# 03_USB.net
KiCad netlist of a schematic drawn in Altium Designer
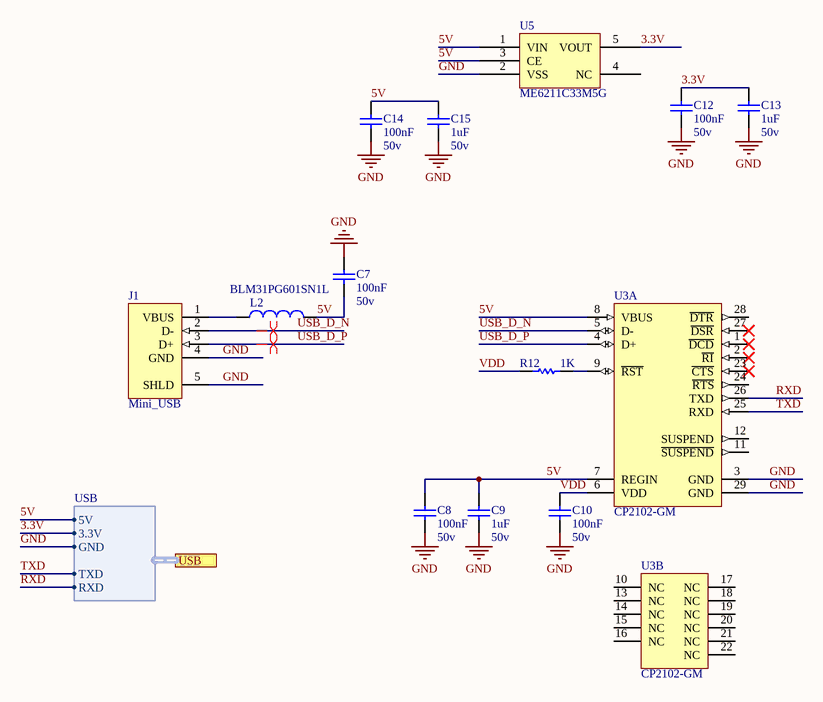
[diagram p0: [03] USB.SchDoc]

(export (version "E")
  (design (tool "Eeschema 10.0.6"))
  (components
    (comp (ref "C7")
      (value "100nF")
      (footprint "MY_0603")
      (description "None polar capacitor")
      (fields (field (name "ASID PART NUMBER") "C-AS") (field (name "VOLTE") "50v"))
      (libsource (lib "Mylib Rev 4") (part "Cap ceramic"))
    )
    (comp (ref "C8")
      (value "100nF")
      (footprint "MY_0603")
      (description "None polar capacitor")
      (fields (field (name "ASID PART NUMBER") "C-AS") (field (name "VOLTE") "50v"))
      (libsource (lib "Mylib Rev 4") (part "Cap ceramic"))
    )
    (comp (ref "C9")
      (value "1uF")
      (footprint "MY_0603")
      (description "None polar capacitor")
      (fields (field (name "ASID PART NUMBER") "C-AS") (field (name "VOLTE") "50v"))
      (libsource (lib "Mylib Rev 4") (part "Cap ceramic"))
    )
    (comp (ref "C10")
      (value "100nF")
      (footprint "MY_0603")
      (description "None polar capacitor")
      (fields (field (name "ASID PART NUMBER") "C-AS") (field (name "VOLTE") "50v"))
      (libsource (lib "Mylib Rev 4") (part "Cap ceramic"))
    )
    (comp (ref "C12")
      (value "100nF")
      (footprint "MY_0603")
      (description "None polar capacitor")
      (fields (field (name "ASID PART NUMBER") "C-AS") (field (name "VOLTE") "50v"))
      (libsource (lib "Mylib Rev 4") (part "Cap ceramic"))
    )
    (comp (ref "C13")
      (value "1uF")
      (footprint "MY_0603")
      (description "None polar capacitor")
      (fields (field (name "ASID PART NUMBER") "C-AS") (field (name "VOLTE") "50v"))
      (libsource (lib "Mylib Rev 4") (part "Cap ceramic"))
    )
    (comp (ref "C14")
      (value "100nF")
      (footprint "MY_0603")
      (description "None polar capacitor")
      (fields (field (name "ASID PART NUMBER") "C-AS") (field (name "VOLTE") "50v"))
      (libsource (lib "Mylib Rev 4") (part "Cap ceramic"))
    )
    (comp (ref "C15")
      (value "1uF")
      (footprint "MY_0603")
      (description "None polar capacitor")
      (fields (field (name "ASID PART NUMBER") "C-AS") (field (name "VOLTE") "50v"))
      (libsource (lib "Mylib Rev 4") (part "Cap ceramic"))
    )
    (comp (ref "J1")
      (value "Mini_USB")
      (footprint "MY_Micro_USB_B")
      (description "USB 2.0, Right Angle, SMT, B Type, Receptacle, 5 Position, Black")
      (fields (field (name "ASID PART NUMBER") "Mini_USB-AS"))
      (libsource (lib "Mylib Rev 4") (part "Mini_USB"))
    )
    (comp (ref "L2")
      (value "BLM31PG601SN1L")
      (footprint "MY_1206")
      (description "Inductor")
      (fields (field (name "ASID PART NUMBER") "Inductor-AS"))
      (libsource (lib "Mylib Rev 4") (part "Inductor"))
    )
    (comp (ref "R12")
      (value "1K")
      (footprint "MY_0603")
      (description "Standard resistor")
      (fields (field (name "ASID PART NUMBER") "Res-AS"))
      (libsource (lib "Mylib Rev 4") (part "Res"))
    )
    (comp (ref "U3")
      (value "CP2102-GM")
      (footprint "SLAB-QFN-28-3125x3125TP_N")
      (description "Single-Chip USB to UART Bridge, 1024 Bytes EEPROM, -40 to 85 degC, 28-pin QFN, Tube")
      (fields (field (name "MANUFACTURER") "Silicon Labs"))
      (libsource (lib "Altium Content Vault") (part "SLAB-CP210X-QFN-28-29"))
    )
    (comp (ref "U5")
      (value "ME6211C33M5G")
      (footprint "MY_SOT23-5")
      (description "High Speed LDO Regulators, High PSRR, Low noise")
      (libsource (lib "Mylib Rev 4") (part "ME6211C33M5G"))
    )
  )
  (nets
    (net (code "2") (name "/3.3V") (class "Default")
      (node (ref "C12") (pin "1") (pinfunction "1_1") (pintype "passive"))
      (node (ref "C13") (pin "1") (pinfunction "1_1") (pintype "passive"))
      (node (ref "U5") (pin "5") (pinfunction "VOUT_5") (pintype "power_in"))
    )
    (net (code "3") (name "/5V") (class "Default")
      (node (ref "C14") (pin "1") (pinfunction "1_1") (pintype "passive"))
      (node (ref "C15") (pin "2") (pinfunction "2_2") (pintype "passive"))
      (node (ref "C7") (pin "2") (pinfunction "2_2") (pintype "passive"))
      (node (ref "C8") (pin "2") (pinfunction "2_2") (pintype "passive"))
      (node (ref "C9") (pin "2") (pinfunction "2_2") (pintype "passive"))
      (node (ref "L2") (pin "2") (pinfunction "2_2") (pintype "passive"))
      (node (ref "U3") (pin "7") (pinfunction "REGIN_7") (pintype "power_in"))
      (node (ref "U3") (pin "8") (pinfunction "VBUS_8") (pintype "input"))
      (node (ref "U5") (pin "1") (pinfunction "VIN_1") (pintype "power_in"))
      (node (ref "U5") (pin "3") (pinfunction "CE_3") (pintype "passive"))
    )
    (net (code "4") (name "/RXD") (class "Default")
      (node (ref "U3") (pin "26") (pinfunction "TXD_26") (pintype "output"))
    )
    (net (code "5") (name "/TXD") (class "Default")
      (node (ref "U3") (pin "25") (pinfunction "RXD_25") (pintype "input"))
    )
    (net (code "6") (name "/USB_D_N") (class "Default")
      (node (ref "J1") (pin "2") (pinfunction "D-_2") (pintype "input"))
      (node (ref "U3") (pin "5") (pinfunction "D-_5") (pintype "bidirectional"))
    )
    (net (code "7") (name "/USB_D_P") (class "Default")
      (node (ref "J1") (pin "3") (pinfunction "D+_3") (pintype "input"))
      (node (ref "U3") (pin "4") (pinfunction "D+_4") (pintype "bidirectional"))
    )
    (net (code "8") (name "/VDD") (class "Default")
      (node (ref "C10") (pin "2") (pinfunction "2_2") (pintype "passive"))
      (node (ref "R12") (pin "1") (pinfunction "1_1") (pintype "passive"))
      (node (ref "U3") (pin "6") (pinfunction "VDD_6") (pintype "power_in"))
    )
    (net (code "10") (name "GND") (class "Default")
      (node (ref "C10") (pin "1") (pinfunction "1_1") (pintype "passive"))
      (node (ref "C12") (pin "2") (pinfunction "2_2") (pintype "passive"))
      (node (ref "C13") (pin "2") (pinfunction "2_2") (pintype "passive"))
      (node (ref "C14") (pin "2") (pinfunction "2_2") (pintype "passive"))
      (node (ref "C15") (pin "1") (pinfunction "1_1") (pintype "passive"))
      (node (ref "C7") (pin "1") (pinfunction "1_1") (pintype "passive"))
      (node (ref "C8") (pin "1") (pinfunction "1_1") (pintype "passive"))
      (node (ref "C9") (pin "1") (pinfunction "1_1") (pintype "passive"))
      (node (ref "J1") (pin "4") (pinfunction "GND_4") (pintype "power_in"))
      (node (ref "J1") (pin "5") (pinfunction "SHLD_5") (pintype "passive"))
      (node (ref "U3") (pin "29") (pinfunction "GND_29") (pintype "power_in"))
      (node (ref "U3") (pin "3") (pinfunction "GND_3") (pintype "power_in"))
      (node (ref "U5") (pin "2") (pinfunction "VSS_2") (pintype "power_in"))
    )
    (net (code "11") (name "Net-(J1-VBUS)") (class "Default")
      (node (ref "J1") (pin "1") (pinfunction "VBUS_1") (pintype "power_in"))
      (node (ref "L2") (pin "1") (pinfunction "1_1") (pintype "passive"))
    )
    (net (code "12") (name "Net-(U3A-~{RST})") (class "Default")
      (node (ref "R12") (pin "2") (pinfunction "2_2") (pintype "passive"))
      (node (ref "U3") (pin "9") (pinfunction "~{RST}_9") (pintype "bidirectional"))
    )
    (net (code "13") (name "unconnected-(U3A-SUSPEND-Pad12)") (class "Default")
      (node (ref "U3") (pin "12") (pinfunction "SUSPEND_12") (pintype "output"))
    )
    (net (code "14") (name "unconnected-(U3A-~{CTS}-Pad23)") (class "Default")
      (node (ref "U3") (pin "23") (pinfunction "~{CTS}_23") (pintype "input+no_connect"))
    )
    (net (code "15") (name "unconnected-(U3A-~{DCD}-Pad1)") (class "Default")
      (node (ref "U3") (pin "1") (pinfunction "~{DCD}_1") (pintype "input+no_connect"))
    )
    (net (code "16") (name "unconnected-(U3A-~{DSR}-Pad27)") (class "Default")
      (node (ref "U3") (pin "27") (pinfunction "~{DSR}_27") (pintype "input+no_connect"))
    )
    (net (code "17") (name "unconnected-(U3A-~{DTR}-Pad28)") (class "Default")
      (node (ref "U3") (pin "28") (pinfunction "~{DTR}_28") (pintype "output"))
    )
    (net (code "18") (name "unconnected-(U3A-~{RI}-Pad2)") (class "Default")
      (node (ref "U3") (pin "2") (pinfunction "~{RI}_2") (pintype "input+no_connect"))
    )
    (net (code "19") (name "unconnected-(U3A-~{RTS}-Pad24)") (class "Default")
      (node (ref "U3") (pin "24") (pinfunction "~{RTS}_24") (pintype "output"))
    )
    (net (code "20") (name "unconnected-(U3A-~{SUSPEND}-Pad11)") (class "Default")
      (node (ref "U3") (pin "11") (pinfunction "~{SUSPEND}_11") (pintype "output"))
    )
    (net (code "21") (name "unconnected-(U3B-NC-Pad10)") (class "Default")
      (node (ref "U3") (pin "10") (pinfunction "NC_10") (pintype "passive"))
    )
    (net (code "22") (name "unconnected-(U3B-NC-Pad13)") (class "Default")
      (node (ref "U3") (pin "13") (pinfunction "NC_13") (pintype "passive"))
    )
    (net (code "23") (name "unconnected-(U3B-NC-Pad14)") (class "Default")
      (node (ref "U3") (pin "14") (pinfunction "NC_14") (pintype "passive"))
    )
    (net (code "24") (name "unconnected-(U3B-NC-Pad15)") (class "Default")
      (node (ref "U3") (pin "15") (pinfunction "NC_15") (pintype "passive"))
    )
    (net (code "25") (name "unconnected-(U3B-NC-Pad16)") (class "Default")
      (node (ref "U3") (pin "16") (pinfunction "NC_16") (pintype "passive"))
    )
    (net (code "26") (name "unconnected-(U3B-NC-Pad17)") (class "Default")
      (node (ref "U3") (pin "17") (pinfunction "NC_17") (pintype "passive"))
    )
    (net (code "27") (name "unconnected-(U3B-NC-Pad18)") (class "Default")
      (node (ref "U3") (pin "18") (pinfunction "NC_18") (pintype "passive"))
    )
    (net (code "28") (name "unconnected-(U3B-NC-Pad19)") (class "Default")
      (node (ref "U3") (pin "19") (pinfunction "NC_19") (pintype "passive"))
    )
    (net (code "29") (name "unconnected-(U3B-NC-Pad20)") (class "Default")
      (node (ref "U3") (pin "20") (pinfunction "NC_20") (pintype "passive"))
    )
    (net (code "30") (name "unconnected-(U3B-NC-Pad21)") (class "Default")
      (node (ref "U3") (pin "21") (pinfunction "NC_21") (pintype "passive"))
    )
    (net (code "31") (name "unconnected-(U3B-NC-Pad22)") (class "Default")
      (node (ref "U3") (pin "22") (pinfunction "NC_22") (pintype "passive"))
    )
    (net (code "32") (name "unconnected-(U5-NC-Pad4)") (class "Default")
      (node (ref "U5") (pin "4") (pinfunction "NC_4") (pintype "passive"))
    )
  )
)
